# schematic.net
KiCad netlist of a schematic drawn in Altium Designer
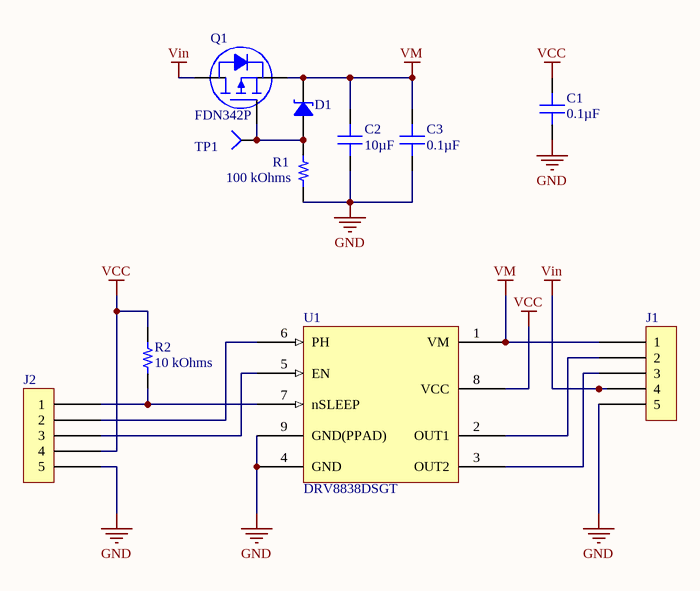
[diagram p0: schematic.SchDoc]

(export (version "E")
  (design (tool "Eeschema 10.0.6"))
  (components
    (comp (ref "C1")
      (value "0.1µF")
      (footprint "CAP 0603_1608")
      (description "CAP CER 0.1UF 16V X7R 0603")
      (fields (field (name "PART NUMBER") "CC0603JRX7R7BB104") (field (name "MANUFACTURER") "Yageo"))
      (libsource (lib "Celestial Altium Library - altium_library") (part "Capacitor"))
    )
    (comp (ref "C2")
      (value "10µF")
      (footprint "CAP 0805_2012")
      (description "CAP CER 10UF 16V X5R 0805")
      (fields (field (name "PART NUMBER") "CC0805KKX5R7BB106") (field (name "MANUFACTURER") "Yageo"))
      (libsource (lib "Celestial Altium Library - altium_library") (part "Capacitor"))
    )
    (comp (ref "C3")
      (value "0.1µF")
      (footprint "CAP 0603_1608")
      (description "CAP CER 0.1UF 16V X7R 0603")
      (fields (field (name "PART NUMBER") "CC0603JRX7R7BB104") (field (name "MANUFACTURER") "Yageo"))
      (libsource (lib "Celestial Altium Library - altium_library") (part "Capacitor"))
    )
    (comp (ref "D1")
      (value "1SMA5921BT3G")
      (footprint "DO214AC SMA")
      (description "DIODE ZENER 6.8V 1.5W SMA")
      (fields (field (name "MANUFACTURER") "ON Semiconductor") (field (name "TOLERANCE") "±5%"))
      (libsource (lib "Celestial Altium Library - altium_library") (part "Diode Zener"))
    )
    (comp (ref "J1") (value "JMP_5") (description "HEADER 5x1") (libsource (lib "") (part "JMP_5_1")))
    (comp (ref "J2") (value "JMP_5") (description "HEADER 5x1") (libsource (lib "MC_V1") (part "JMP_5")))
    (comp (ref "Q1")
      (value "FDN342P")
      (footprint "DIODES SOT-23-3")
      (description "MOSFET P-CH 20V 2A SSOT-3")
      (libsource (lib "Celestial Altium Library - altium_library") (part "DIODES MOSFET P-CH SOT-23-3"))
    )
    (comp (ref "R1")
      (value "100 kOhms")
      (footprint "RES 0603_1608")
      (description "RES SMD 100K OHM 0.5% 1/10W 0603")
      (fields (field (name "PART NUMBER") "RT0603DRE07100KL") (field (name "MANUFACTURER") "Yageo"))
      (libsource (lib "Celestial Altium Library - altium_library") (part "Resistor"))
    )
    (comp (ref "R2")
      (value "10 kOhms")
      (footprint "RES 0603_1608")
      (description "RES SMD 10K OHM 1% 1/10W 0603")
      (fields (field (name "PART NUMBER") "AF0603FR-0710KL") (field (name "MANUFACTURER") "Yageo"))
      (libsource (lib "Celestial Altium Library - altium_library") (part "Resistor"))
    )
    (comp (ref "TP1")
      (value "TESTPOINT_SMD")
      (footprint "TESTPOINT")
      (libsource (lib "UWRT_Schematic_Library_2020") (part "TESTPOINT_SMD"))
    )
    (comp (ref "U1")
      (value "DRV8838DSGT")
      (description "H-bridge Single Channel Motor Driver IC")
      (fields (field (name "MANUFACTURER PART NUMBER 1") "DRV8838DSGT"))
      (libsource (lib "MC_V1") (part "DRV8838DSGT"))
    )
  )
  (nets
    (net (code "1") (name "GND") (class "Default")
      (node (ref "C1") (pin "1") (pinfunction "1_1") (pintype "passive"))
      (node (ref "C2") (pin "1") (pinfunction "1_1") (pintype "passive"))
      (node (ref "C3") (pin "1") (pinfunction "1_1") (pintype "passive"))
      (node (ref "J1") (pin "5") (pinfunction "5_5") (pintype "passive"))
      (node (ref "J2") (pin "5") (pinfunction "5_5") (pintype "passive"))
      (node (ref "R1") (pin "1") (pinfunction "1_1") (pintype "passive"))
      (node (ref "U1") (pin "4") (pinfunction "GND_4") (pintype "passive"))
      (node (ref "U1") (pin "9") (pinfunction "GND(PPAD)_9") (pintype "passive"))
    )
    (net (code "2") (name "Net-(Q1-G)") (class "Default")
      (node (ref "D1") (pin "1") (pinfunction "1_1") (pintype "passive"))
      (node (ref "Q1") (pin "1") (pinfunction "G_1") (pintype "passive"))
      (node (ref "R1") (pin "2") (pinfunction "2_2") (pintype "passive"))
      (node (ref "TP1") (pin "1") (pinfunction "=value_1") (pintype "passive"))
    )
    (net (code "3") (name "Net-(U1-EN)") (class "Default")
      (node (ref "J2") (pin "3") (pinfunction "3_3") (pintype "passive"))
      (node (ref "U1") (pin "5") (pinfunction "EN_5") (pintype "input"))
    )
    (net (code "4") (name "Net-(U1-OUT1)") (class "Default")
      (node (ref "J1") (pin "2") (pinfunction "2_2") (pintype "passive"))
      (node (ref "U1") (pin "2") (pinfunction "OUT1_2") (pintype "passive"))
    )
    (net (code "5") (name "Net-(U1-OUT2)") (class "Default")
      (node (ref "J1") (pin "3") (pinfunction "3_3") (pintype "passive"))
      (node (ref "U1") (pin "3") (pinfunction "OUT2_3") (pintype "passive"))
    )
    (net (code "6") (name "Net-(U1-PH)") (class "Default")
      (node (ref "J2") (pin "2") (pinfunction "2_2") (pintype "passive"))
      (node (ref "U1") (pin "6") (pinfunction "PH_6") (pintype "input"))
    )
    (net (code "7") (name "Net-(U1-nSLEEP)") (class "Default")
      (node (ref "J2") (pin "1") (pinfunction "1_1") (pintype "passive"))
      (node (ref "R2") (pin "1") (pinfunction "1_1") (pintype "passive"))
      (node (ref "U1") (pin "7") (pinfunction "nSLEEP_7") (pintype "input"))
    )
    (net (code "8") (name "VCC") (class "Default")
      (node (ref "C1") (pin "2") (pinfunction "2_2") (pintype "passive"))
      (node (ref "J2") (pin "4") (pinfunction "4_4") (pintype "passive"))
      (node (ref "R2") (pin "2") (pinfunction "2_2") (pintype "passive"))
      (node (ref "U1") (pin "8") (pinfunction "VCC_8") (pintype "passive"))
    )
    (net (code "9") (name "VM") (class "Default")
      (node (ref "C2") (pin "2") (pinfunction "2_2") (pintype "passive"))
      (node (ref "C3") (pin "2") (pinfunction "2_2") (pintype "passive"))
      (node (ref "D1") (pin "2") (pinfunction "2_2") (pintype "passive"))
      (node (ref "J1") (pin "1") (pinfunction "1_1") (pintype "passive"))
      (node (ref "Q1") (pin "2") (pinfunction "S_2") (pintype "passive"))
      (node (ref "U1") (pin "1") (pinfunction "VM_1") (pintype "passive"))
    )
    (net (code "10") (name "Vin") (class "Default")
      (node (ref "J1") (pin "4") (pinfunction "4_4") (pintype "passive"))
      (node (ref "Q1") (pin "3") (pinfunction "D_3") (pintype "passive"))
    )
  )
)
